# RS485.net
KiCad netlist of a schematic drawn in Altium Designer
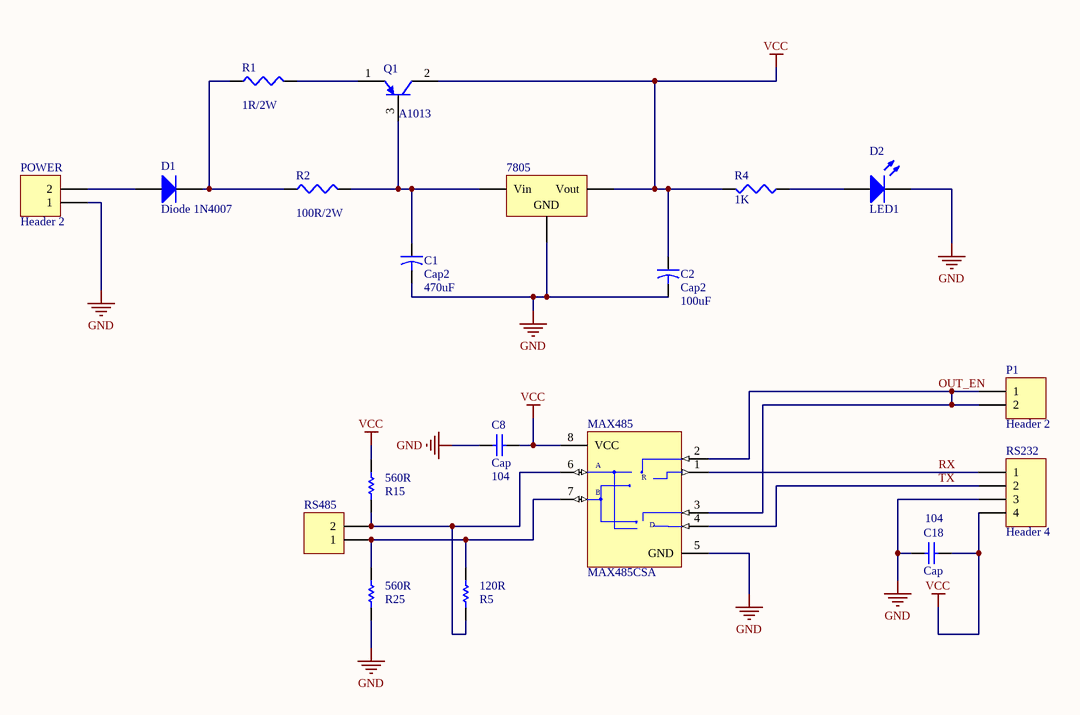
[diagram p0: RS485.SchDoc]

(export (version "E")
  (design (tool "Eeschema 10.0.6"))
  (components
    (comp (ref "7805")
      (value "Volt Reg")
      (footprint "Device:78xx_NO")
      (description "Voltage Regulator")
      (fields (field (name "PUBLISHER") "Altium Limited"))
      (libsource (lib "Miscellaneous Devices") (part "Volt Reg"))
    )
    (comp (ref "C1")
      (value "Cap2")
      (footprint "Device:tu 10uF")
      (description "Capacitor")
      (fields (field (name "ALTIUM_VALUE") "470uF") (field (name "PUBLISHER") "Altium Limited"))
      (libsource (lib "Miscellaneous Devices") (part "Cap2"))
    )
    (comp (ref "C2")
      (value "Cap2")
      (footprint "Device:tu 10uF")
      (description "Capacitor")
      (fields (field (name "ALTIUM_VALUE") "100uF") (field (name "PUBLISHER") "Altium Limited"))
      (libsource (lib "Miscellaneous Devices") (part "Cap2"))
    )
    (comp (ref "C8")
      (value "Cap")
      (footprint "Device:tu_gom")
      (description "Capcitor")
      (fields (field (name "ALTIUM_VALUE") "104"))
      (libsource (lib "Device_Component") (part "Ceramic"))
    )
    (comp (ref "C18")
      (value "Cap")
      (footprint "Device:tu_gom")
      (description "Capcitor")
      (fields (field (name "ALTIUM_VALUE") "104"))
      (libsource (lib "Device_Component") (part "Ceramic"))
    )
    (comp (ref "D1")
      (value "Diode 1N4007")
      (footprint "Device:D_2A")
      (description "1 Amp General Purpose Rectifier")
      (fields (field (name "PUBLISHER") "Altium Limited"))
      (libsource (lib "Miscellaneous Devices") (part "Diode 1N4007"))
    )
    (comp (ref "D2")
      (value "LED1")
      (footprint "Device:LED_3")
      (description "Typical RED GaAs LED")
      (fields (field (name "PUBLISHER") "Altium Limited"))
      (libsource (lib "Miscellaneous Devices") (part "LED1"))
    )
    (comp (ref "MAX485")
      (value "MAX485CSA")
      (footprint "Maxim Communication Transceiver:PA8")
      (description "Low-Power, Slew-Rate-Limited RS-485/RS-422 Transceiver")
      (fields (field (name "PUBLISHER") "Altium Limited"))
      (libsource (lib "Maxim Communication Transceiver") (part "MAX485CSA"))
    )
    (comp (ref "P1")
      (value "Header 2")
      (footprint "HDR1X2")
      (description "Header, 2-Pin")
      (fields (field (name "PUBLISHER") "Altium Limited"))
      (libsource (lib "") (part "Header 2_1"))
    )
    (comp (ref "POWER")
      (value "Header 2")
      (footprint "Device:Header2 - duplicate")
      (description "Header, 2-Pin")
      (fields (field (name "PUBLISHER") "Altium Limited"))
      (libsource (lib "Miscellaneous Connectors") (part "Header 2"))
    )
    (comp (ref "Q1")
      (value "A1013")
      (footprint "Device:D468/A1013")
      (description "PNP Bipolar Transistor")
      (fields (field (name "PUBLISHER") "Altium Limited"))
      (libsource (lib "Miscellaneous Devices") (part "PNP"))
    )
    (comp (ref "R1")
      (value "1R/2W")
      (footprint "Device:R_CS0R22/2W")
      (description "Resistor")
      (fields (field (name "Comment") "Res3") (field (name "PUBLISHER") "Altium Limited"))
      (libsource (lib "Miscellaneous Devices") (part "Res3"))
    )
    (comp (ref "R2")
      (value "100R/2W")
      (footprint "Device:R_CS0R22/2W")
      (description "Resistor")
      (fields (field (name "Comment") "Res3") (field (name "PUBLISHER") "Altium Limited"))
      (libsource (lib "Miscellaneous Devices") (part "Res3"))
    )
    (comp (ref "R4")
      (value "1K")
      (footprint "Device:R_Nor")
      (description "Resistor")
      (fields (field (name "Comment") "Res3") (field (name "PUBLISHER") "Altium Limited"))
      (libsource (lib "Miscellaneous Devices") (part "Res3"))
    )
    (comp (ref "R5")
      (value "120R")
      (footprint "Device:R_Nor")
      (libsource (lib "Device_Component") (part "Res"))
    )
    (comp (ref "R15")
      (value "560R")
      (footprint "Device:R_Nor")
      (libsource (lib "Device_Component") (part "Res"))
    )
    (comp (ref "R25")
      (value "560R")
      (footprint "Device:R_Nor")
      (libsource (lib "Device_Component") (part "Res"))
    )
    (comp (ref "RS232")
      (value "Header 4")
      (footprint "Device:Header4")
      (description "Header, 4-Pin")
      (fields (field (name "PUBLISHER") "Altium Limited"))
      (libsource (lib "Miscellaneous Connectors") (part "Header 4"))
    )
    (comp (ref "RS485")
      (value "Header 2")
      (footprint "Device:Header2 - duplicate")
      (description "Header, 2-Pin")
      (fields (field (name "PUBLISHER") "Altium Limited"))
      (libsource (lib "Miscellaneous Connectors") (part "Header 2"))
    )
  )
  (nets
    (net (code "1") (name "/OUT_EN") (class "Default")
      (node (ref "MAX485") (pin "2") (pinfunction "~{RE}_2") (pintype "input"))
      (node (ref "MAX485") (pin "3") (pinfunction "DE_3") (pintype "input"))
      (node (ref "P1") (pin "1") (pinfunction "1_1") (pintype "passive"))
      (node (ref "P1") (pin "2") (pinfunction "2_2") (pintype "passive"))
    )
    (net (code "2") (name "/RX") (class "Default")
      (node (ref "MAX485") (pin "1") (pinfunction "RO_1") (pintype "output"))
      (node (ref "RS232") (pin "1") (pinfunction "1_1") (pintype "passive"))
    )
    (net (code "3") (name "/TX") (class "Default")
      (node (ref "MAX485") (pin "4") (pinfunction "DI_4") (pintype "input"))
      (node (ref "RS232") (pin "2") (pinfunction "2_2") (pintype "passive"))
    )
    (net (code "4") (name "GND") (class "Default")
      (node (ref "7805") (pin "2") (pinfunction "GND_2") (pintype "passive"))
      (node (ref "C1") (pin "2") (pinfunction "2_2") (pintype "passive"))
      (node (ref "C18") (pin "1") (pinfunction "1_1") (pintype "passive"))
      (node (ref "C2") (pin "2") (pinfunction "2_2") (pintype "passive"))
      (node (ref "C8") (pin "1") (pinfunction "1_1") (pintype "passive"))
      (node (ref "D2") (pin "2") (pinfunction "K_2") (pintype "passive"))
      (node (ref "MAX485") (pin "5") (pinfunction "GND_5") (pintype "power_in"))
      (node (ref "POWER") (pin "1") (pinfunction "1_1") (pintype "passive"))
      (node (ref "R25") (pin "1") (pinfunction "1_1") (pintype "passive"))
      (node (ref "RS232") (pin "3") (pinfunction "3_3") (pintype "passive"))
    )
    (net (code "5") (name "Net-(7805-Vin)") (class "Default")
      (node (ref "7805") (pin "1") (pinfunction "Vin_1") (pintype "passive"))
      (node (ref "C1") (pin "1") (pinfunction "1_1") (pintype "passive"))
      (node (ref "Q1") (pin "3") (pinfunction "B_3") (pintype "passive"))
      (node (ref "R2") (pin "2") (pinfunction "2_2") (pintype "passive"))
    )
    (net (code "6") (name "Net-(D1-A)") (class "Default")
      (node (ref "D1") (pin "1") (pinfunction "A_1") (pintype "passive"))
      (node (ref "POWER") (pin "2") (pinfunction "2_2") (pintype "passive"))
    )
    (net (code "7") (name "Net-(D1-K)") (class "Default")
      (node (ref "D1") (pin "2") (pinfunction "K_2") (pintype "passive"))
      (node (ref "R1") (pin "1") (pinfunction "1_1") (pintype "passive"))
      (node (ref "R2") (pin "1") (pinfunction "1_1") (pintype "passive"))
    )
    (net (code "8") (name "Net-(D2-A)") (class "Default")
      (node (ref "D2") (pin "1") (pinfunction "A_1") (pintype "passive"))
      (node (ref "R4") (pin "1") (pinfunction "1_1") (pintype "passive"))
    )
    (net (code "9") (name "Net-(MAX485-A)") (class "Default")
      (node (ref "MAX485") (pin "6") (pinfunction "A_6") (pintype "bidirectional"))
      (node (ref "R15") (pin "1") (pinfunction "1_1") (pintype "passive"))
      (node (ref "R5") (pin "1") (pinfunction "1_1") (pintype "passive"))
      (node (ref "RS485") (pin "2") (pinfunction "2_2") (pintype "passive"))
    )
    (net (code "10") (name "Net-(MAX485-B)") (class "Default")
      (node (ref "MAX485") (pin "7") (pinfunction "B_7") (pintype "bidirectional"))
      (node (ref "R25") (pin "2") (pinfunction "2_2") (pintype "passive"))
      (node (ref "R5") (pin "2") (pinfunction "2_2") (pintype "passive"))
      (node (ref "RS485") (pin "1") (pinfunction "1_1") (pintype "passive"))
    )
    (net (code "11") (name "Net-(Q1-E)") (class "Default")
      (node (ref "Q1") (pin "1") (pinfunction "E_1") (pintype "passive"))
      (node (ref "R1") (pin "2") (pinfunction "2_2") (pintype "passive"))
    )
    (net (code "12") (name "VCC") (class "Default")
      (node (ref "7805") (pin "3") (pinfunction "Vout_3") (pintype "passive"))
      (node (ref "C18") (pin "2") (pinfunction "2_2") (pintype "passive"))
      (node (ref "C2") (pin "1") (pinfunction "1_1") (pintype "passive"))
      (node (ref "C8") (pin "2") (pinfunction "2_2") (pintype "passive"))
      (node (ref "MAX485") (pin "8") (pinfunction "VCC_8") (pintype "power_in"))
      (node (ref "Q1") (pin "2") (pinfunction "C_2") (pintype "passive"))
      (node (ref "R15") (pin "2") (pinfunction "2_2") (pintype "passive"))
      (node (ref "R4") (pin "2") (pinfunction "2_2") (pintype "passive"))
      (node (ref "RS232") (pin "4") (pinfunction "4_4") (pintype "passive"))
    )
  )
)
